# Sheet3.net
KiCad netlist of a schematic drawn in Altium Designer
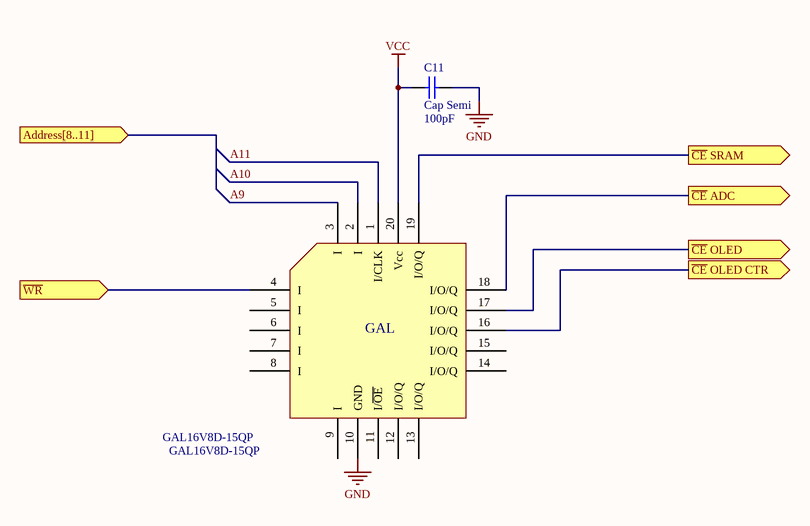
[diagram p0: Sheet3.SchDoc]

(export (version "E")
  (design (tool "Eeschema 10.0.6"))
  (components
    (comp (ref "C11")
      (value "Cap Semi")
      (footprint "C1210")
      (description "Capacitor (Semiconductor SIM Model)")
      (fields (field (name "ALTIUM_VALUE") "100pF") (field (name "PUBLISHER") "Altium Limited"))
      (libsource (lib "Miscellaneous Devices") (part "Cap Semi"))
    )
    (comp (ref "GAL16V8D-15QP")
      (value "GAL16V8D-15QP")
      (footprint "GAL 16V8D-10LJ/-10QL PLCC 20-PIN")
      (description "GAL - Generic Array Logic")
      (libsource (lib "IIDKLib") (part "GAL16V8D-15QP"))
    )
  )
  (nets
    (net (code "5") (name "/A9") (class "Default")
      (node (ref "GAL16V8D-15QP") (pin "3") (pinfunction "I_3") (pintype "passive"))
    )
    (net (code "6") (name "/A10") (class "Default")
      (node (ref "GAL16V8D-15QP") (pin "2") (pinfunction "I_2") (pintype "passive"))
    )
    (net (code "7") (name "/A11") (class "Default")
      (node (ref "GAL16V8D-15QP") (pin "1") (pinfunction "I/CLK_1") (pintype "passive"))
    )
    (net (code "9") (name "/~{CE} ADC") (class "Default")
      (node (ref "GAL16V8D-15QP") (pin "18") (pinfunction "I/O/Q_18") (pintype "passive"))
    )
    (net (code "10") (name "/~{CE} OLED") (class "Default")
      (node (ref "GAL16V8D-15QP") (pin "17") (pinfunction "I/O/Q_17") (pintype "passive"))
    )
    (net (code "11") (name "/~{CE} OLED CTR") (class "Default")
      (node (ref "GAL16V8D-15QP") (pin "16") (pinfunction "I/O/Q_16") (pintype "passive"))
    )
    (net (code "12") (name "/~{CE} SRAM") (class "Default")
      (node (ref "GAL16V8D-15QP") (pin "19") (pinfunction "I/O/Q_19") (pintype "passive"))
    )
    (net (code "13") (name "/~{WR}") (class "Default")
      (node (ref "GAL16V8D-15QP") (pin "4") (pinfunction "I_4") (pintype "passive"))
    )
    (net (code "14") (name "GND") (class "Default")
      (node (ref "C11") (pin "1") (pinfunction "1_1") (pintype "passive"))
      (node (ref "GAL16V8D-15QP") (pin "10") (pinfunction "GND_10") (pintype "power_in"))
    )
    (net (code "15") (name "VCC") (class "Default")
      (node (ref "C11") (pin "2") (pinfunction "2_2") (pintype "passive"))
      (node (ref "GAL16V8D-15QP") (pin "20") (pinfunction "Vcc_20") (pintype "power_in"))
    )
    (net (code "16") (name "unconnected-(GAL16V8D-15QP-I-Pad5)") (class "Default")
      (node (ref "GAL16V8D-15QP") (pin "5") (pinfunction "I_5") (pintype "passive"))
    )
    (net (code "17") (name "unconnected-(GAL16V8D-15QP-I-Pad6)") (class "Default")
      (node (ref "GAL16V8D-15QP") (pin "6") (pinfunction "I_6") (pintype "passive"))
    )
    (net (code "18") (name "unconnected-(GAL16V8D-15QP-I-Pad7)") (class "Default")
      (node (ref "GAL16V8D-15QP") (pin "7") (pinfunction "I_7") (pintype "passive"))
    )
    (net (code "19") (name "unconnected-(GAL16V8D-15QP-I-Pad8)") (class "Default")
      (node (ref "GAL16V8D-15QP") (pin "8") (pinfunction "I_8") (pintype "passive"))
    )
    (net (code "20") (name "unconnected-(GAL16V8D-15QP-I-Pad9)") (class "Default")
      (node (ref "GAL16V8D-15QP") (pin "9") (pinfunction "I_9") (pintype "passive"))
    )
    (net (code "21") (name "unconnected-(GAL16V8D-15QP-I{slash}O{slash}Q-Pad12)") (class "Default")
      (node (ref "GAL16V8D-15QP") (pin "12") (pinfunction "I/O/Q_12") (pintype "passive"))
    )
    (net (code "22") (name "unconnected-(GAL16V8D-15QP-I{slash}O{slash}Q-Pad13)") (class "Default")
      (node (ref "GAL16V8D-15QP") (pin "13") (pinfunction "I/O/Q_13") (pintype "passive"))
    )
    (net (code "23") (name "unconnected-(GAL16V8D-15QP-I{slash}O{slash}Q-Pad14)") (class "Default")
      (node (ref "GAL16V8D-15QP") (pin "14") (pinfunction "I/O/Q_14") (pintype "passive"))
    )
    (net (code "24") (name "unconnected-(GAL16V8D-15QP-I{slash}O{slash}Q-Pad15)") (class "Default")
      (node (ref "GAL16V8D-15QP") (pin "15") (pinfunction "I/O/Q_15") (pintype "passive"))
    )
    (net (code "25") (name "unconnected-(GAL16V8D-15QP-I{slash}~{OE}-Pad11)") (class "Default")
      (node (ref "GAL16V8D-15QP") (pin "11") (pinfunction "I/~{OE}_11") (pintype "passive"))
    )
  )
)
